# design.net
KiCad netlist of a schematic drawn in Altium Designer
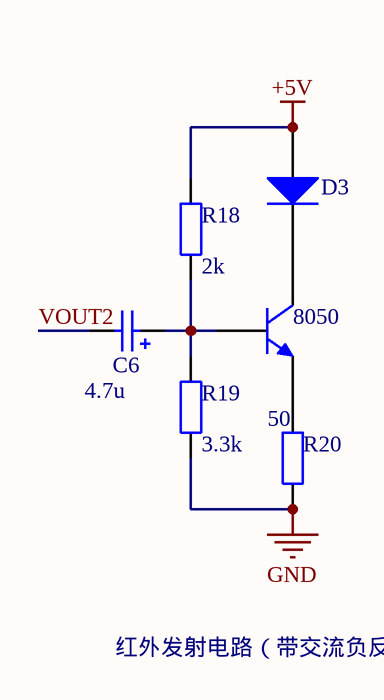
[diagram p0: 三级管红外发射.SchDoc]

(export (version "E")
  (design (tool "Eeschema 10.0.6"))
  (components
    (comp (ref "8050")
      (value "NPN")
      (footprint "TO-226")
      (description "NPN Bipolar Transistor")
      (fields (field (name "PUBLISHER") "Altium Limited"))
      (libsource (lib "Miscellaneous Devices") (part "NPN"))
    )
    (comp (ref "C6")
      (value "电解电容")
      (footprint "电解电容")
      (fields (field (name "ALTIUM_UNNAMED_1") "4.7u"))
      (libsource (lib "自制库（原理图文件）") (part "电解电容"))
    )
    (comp (ref "D3")
      (value "Diode")
      (footprint "SMC")
      (description "Default Diode")
      (fields (field (name "PUBLISHER") "Altium Limited"))
      (libsource (lib "Miscellaneous Devices") (part "Diode"))
    )
    (comp (ref "R18")
      (value "2k")
      (footprint "AXIAL-0.4")
      (description "Resistor")
      (fields (field (name "Comment") "Res2") (field (name "PUBLISHER") "Altium Limited"))
      (libsource (lib "Miscellaneous Devices") (part "Res2"))
    )
    (comp (ref "R19")
      (value "3.3k")
      (footprint "AXIAL-0.4")
      (description "Resistor")
      (fields (field (name "Comment") "Res2") (field (name "PUBLISHER") "Altium Limited"))
      (libsource (lib "Miscellaneous Devices") (part "Res2"))
    )
    (comp (ref "R20")
      (value "50")
      (footprint "AXIAL-0.4")
      (description "Resistor")
      (fields (field (name "Comment") "Res2") (field (name "PUBLISHER") "Altium Limited"))
      (libsource (lib "Miscellaneous Devices") (part "Res2"))
    )
  )
  (nets
    (net (code "1") (name "+5V") (class "Default")
      (node (ref "D3") (pin "1") (pinfunction "A_1") (pintype "passive"))
      (node (ref "R18") (pin "2") (pinfunction "2_2") (pintype "passive"))
    )
    (net (code "2") (name "/VOUT2") (class "Default")
      (node (ref "C6") (pin "2") (pinfunction "2_2") (pintype "passive"))
    )
    (net (code "3") (name "GND") (class "Default")
      (node (ref "R19") (pin "1") (pinfunction "1_1") (pintype "passive"))
      (node (ref "R20") (pin "1") (pinfunction "1_1") (pintype "passive"))
    )
    (net (code "4") (name "Net-(8050-B)") (class "Default")
      (node (ref "8050") (pin "2") (pinfunction "B_2") (pintype "passive"))
      (node (ref "C6") (pin "1") (pinfunction "1_1") (pintype "passive"))
      (node (ref "R18") (pin "1") (pinfunction "1_1") (pintype "passive"))
      (node (ref "R19") (pin "2") (pinfunction "2_2") (pintype "passive"))
    )
    (net (code "5") (name "Net-(8050-C)") (class "Default")
      (node (ref "8050") (pin "1") (pinfunction "C_1") (pintype "passive"))
      (node (ref "D3") (pin "2") (pinfunction "K_2") (pintype "passive"))
    )
    (net (code "6") (name "Net-(8050-E)") (class "Default")
      (node (ref "8050") (pin "3") (pinfunction "E_3") (pintype "passive"))
      (node (ref "R20") (pin "2") (pinfunction "2_2") (pintype "passive"))
    )
  )
)
